# Power.net
KiCad netlist of a schematic drawn in Altium Designer
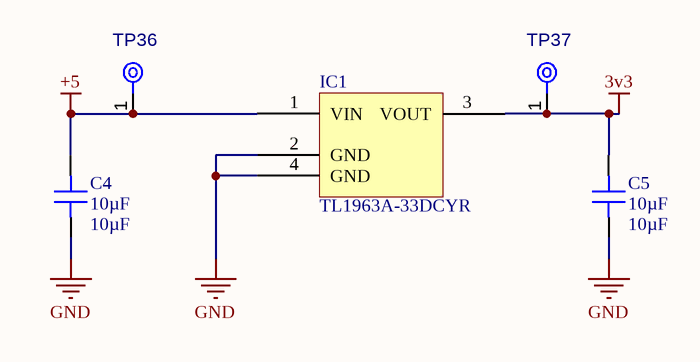
[diagram p0: Power.SchDoc]

(export (version "E")
  (design (tool "Eeschema 10.0.6"))
  (components
    (comp (ref "C4")
      (value "10µF")
      (footprint "CAP 0805_2012")
      (description "CAP CER 10UF 10V X5R 0805")
      (fields (field (name "PART NUMBER") "0805ZD106KAT4A") (field (name "ALTIUM_VALUE") "10µF"))
      (libsource (lib "Celestial Altium Library - altium_library") (part "Capacitor"))
    )
    (comp (ref "C5")
      (value "10µF")
      (footprint "CAP 0805_2012")
      (description "CAP CER 10UF 10V X5R 0805")
      (fields (field (name "PART NUMBER") "0805ZD106KAT4A") (field (name "ALTIUM_VALUE") "10µF"))
      (libsource (lib "Celestial Altium Library - altium_library") (part "Capacitor"))
    )
    (comp (ref "IC1")
      (value "TL1963A-33DCYR")
      (footprint "TI SOT-223 DCY")
      (description "IC REG LINEAR 3.3V 1.5A SOT223-4")
      (fields (field (name "MANUFACTURER") "Texas Instruments"))
      (libsource (lib "Celestial Altium Library - altium_library") (part "TI TL1963A DCY"))
    )
    (comp (ref "TP36")
      (value "TPAD1.0R")
      (footprint "TP06R")
      (description "1.0mm round testpoint")
      (libsource (lib "Cuvos Pty Ltd") (part "CMP-001-0001-4"))
    )
    (comp (ref "TP37")
      (value "TPAD1.0R")
      (footprint "TP06R")
      (description "1.0mm round testpoint")
      (libsource (lib "Cuvos Pty Ltd") (part "CMP-001-0001-4"))
    )
  )
  (nets
    (net (code "1") (name "+5") (class "Default")
      (node (ref "C4") (pin "2") (pinfunction "2_2") (pintype "passive"))
      (node (ref "IC1") (pin "1") (pinfunction "VIN_1") (pintype "passive"))
      (node (ref "TP36") (pin "1") (pinfunction "TP_1") (pintype "passive"))
    )
    (net (code "2") (name "3v3") (class "Default")
      (node (ref "C5") (pin "2") (pinfunction "2_2") (pintype "passive"))
      (node (ref "IC1") (pin "3") (pinfunction "VOUT_3") (pintype "passive"))
      (node (ref "TP37") (pin "1") (pinfunction "TP_1") (pintype "passive"))
    )
    (net (code "3") (name "GND") (class "Default")
      (node (ref "C4") (pin "1") (pinfunction "1_1") (pintype "passive"))
      (node (ref "C5") (pin "1") (pinfunction "1_1") (pintype "passive"))
      (node (ref "IC1") (pin "2") (pinfunction "GND_2") (pintype "passive"))
      (node (ref "IC1") (pin "4") (pinfunction "GND_4") (pintype "passive"))
    )
  )
)
